# SIXXY_00.net
KiCad netlist of a schematic drawn in Altium Designer
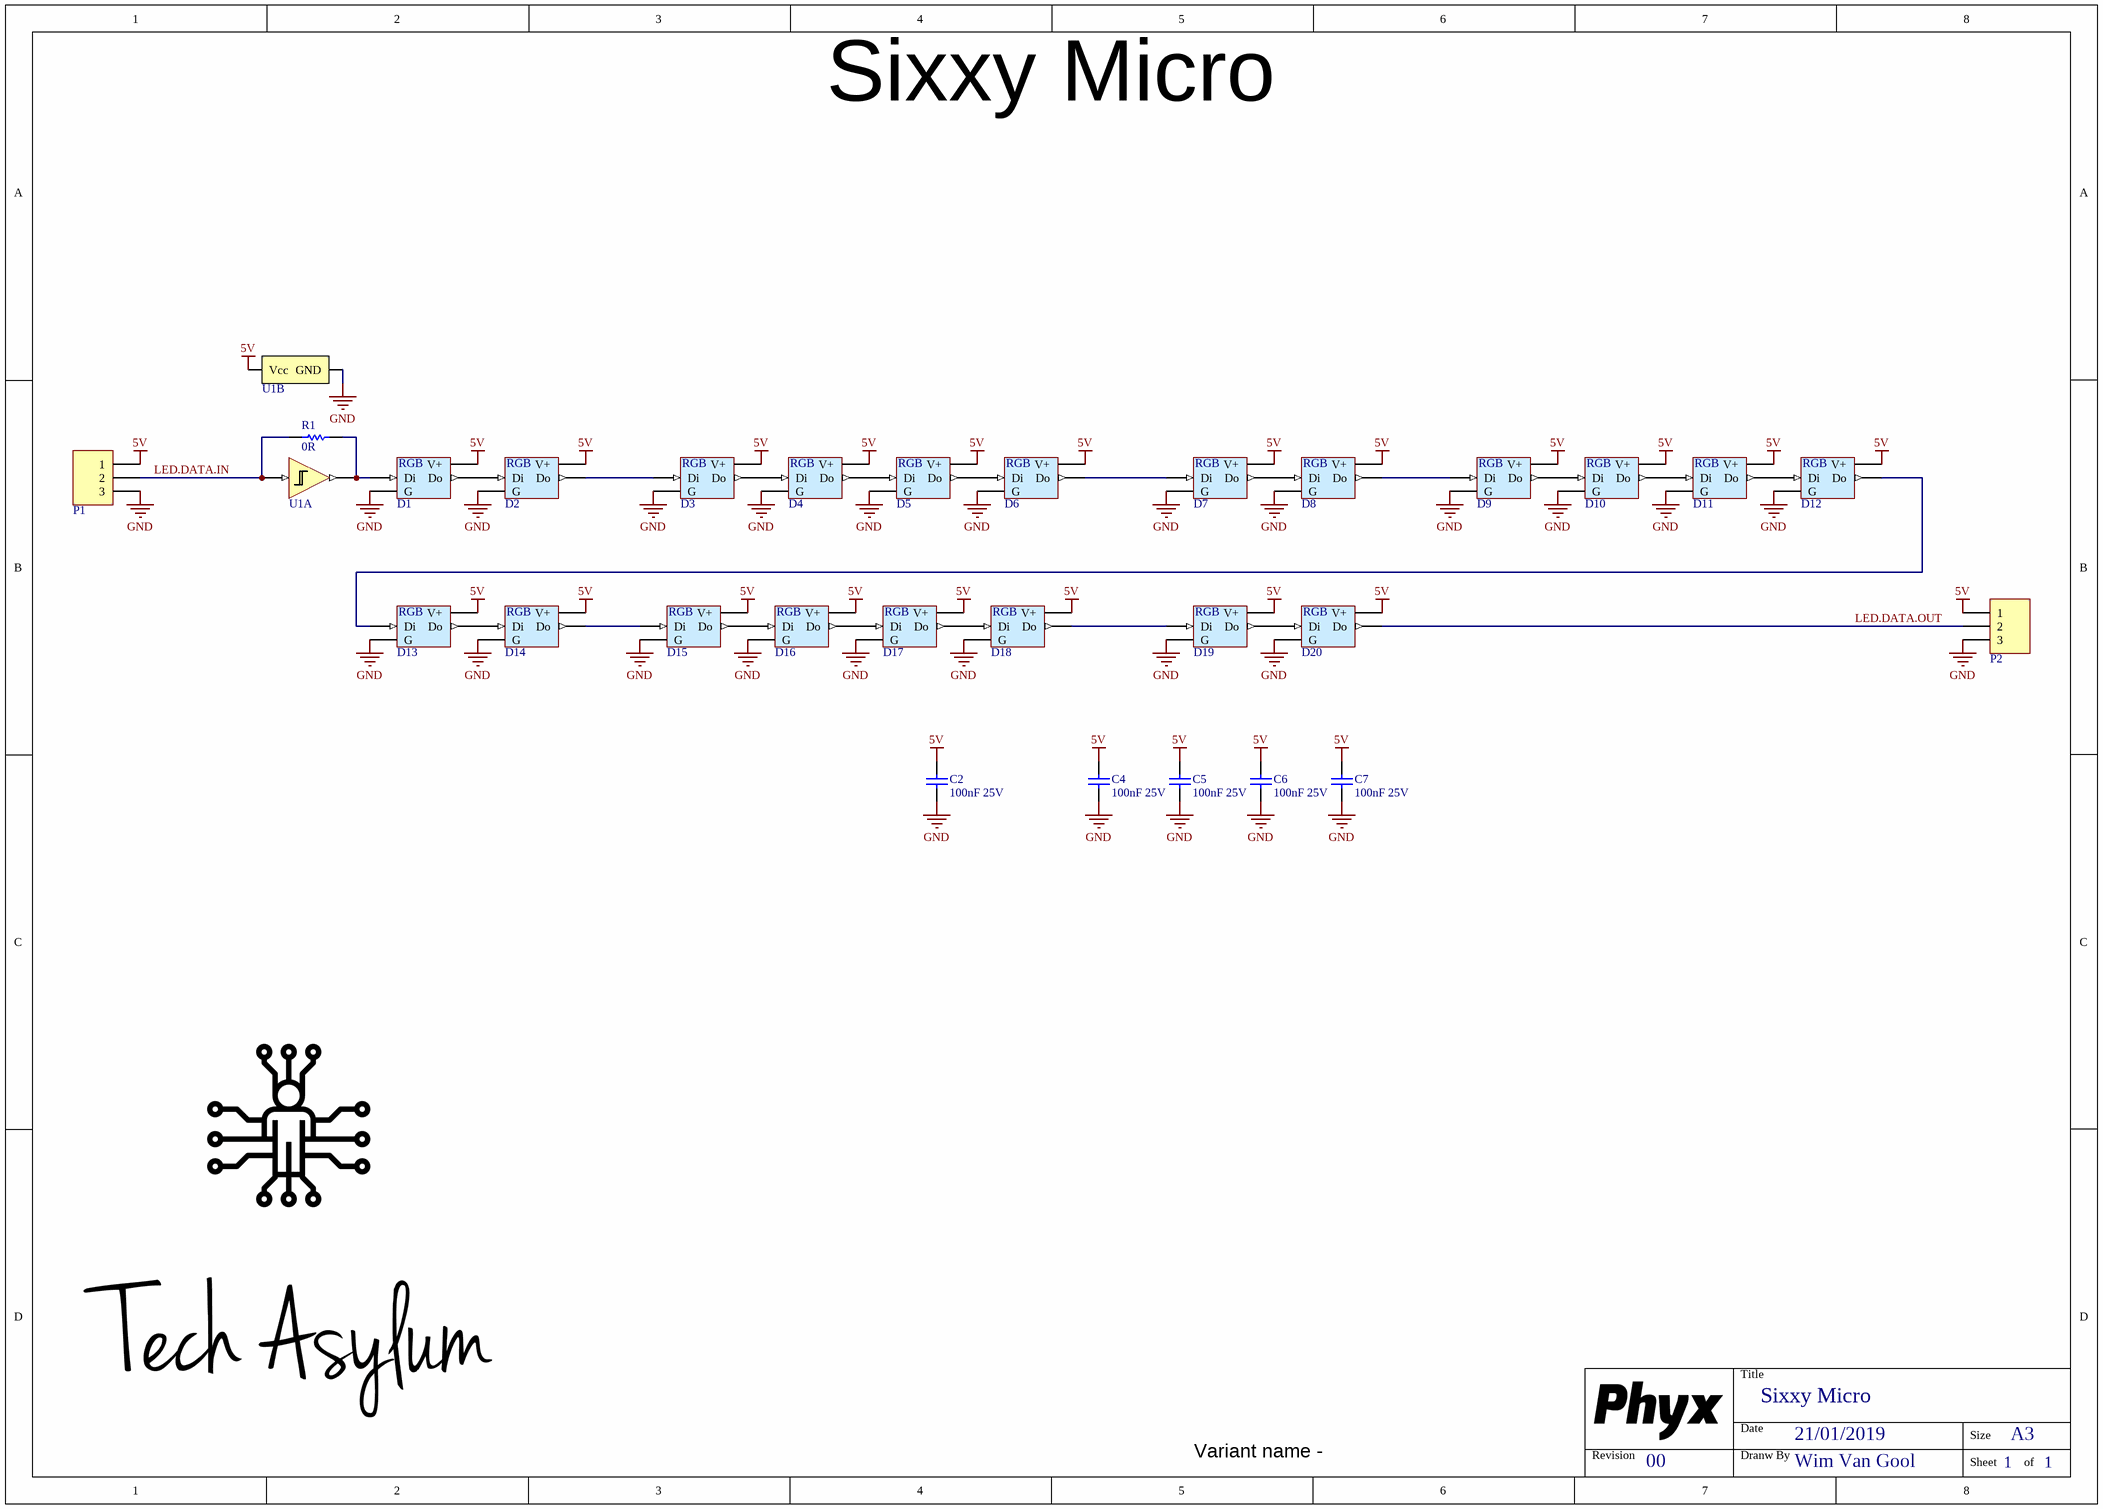
[diagram p0: SIXXY_00.SchDoc]

(export (version "E")
  (design (tool "Eeschema 10.0.6"))
  (components
    (comp (ref "C2")
      (value "100nF 25V")
      (footprint "C0603_N")
      (description "Capacitor Ceramic")
      (fields (field (name "Comment") "CAP_CERAMIC"))
      (libsource (lib "Phyx_Components") (part "CAP_CERAMIC"))
    )
    (comp (ref "C4")
      (value "100nF 25V")
      (footprint "C0603_N")
      (description "Capacitor Ceramic")
      (fields (field (name "Comment") "CAP_CERAMIC"))
      (libsource (lib "Phyx_Components") (part "CAP_CERAMIC"))
    )
    (comp (ref "C5")
      (value "100nF 25V")
      (footprint "C0603_N")
      (description "Capacitor Ceramic")
      (fields (field (name "Comment") "CAP_CERAMIC"))
      (libsource (lib "Phyx_Components") (part "CAP_CERAMIC"))
    )
    (comp (ref "C6")
      (value "100nF 25V")
      (footprint "C0603_N")
      (description "Capacitor Ceramic")
      (fields (field (name "Comment") "CAP_CERAMIC"))
      (libsource (lib "Phyx_Components") (part "CAP_CERAMIC"))
    )
    (comp (ref "C7")
      (value "100nF 25V")
      (footprint "C0603_N")
      (description "Capacitor Ceramic")
      (fields (field (name "Comment") "CAP_CERAMIC"))
      (libsource (lib "Phyx_Components") (part "CAP_CERAMIC"))
    )
    (comp (ref "D1")
      (value "WS2812 based digital RGB LED 2022 package")
      (footprint "LED_2022_WS2812B")
      (description "=Description")
      (libsource (lib "Phyx_Components") (part "LED_RGB_WS2812B_2022"))
    )
    (comp (ref "D2")
      (value "WS2812 based digital RGB LED 2022 package")
      (footprint "LED_2022_WS2812B")
      (description "=Description")
      (libsource (lib "Phyx_Components") (part "LED_RGB_WS2812B_2022"))
    )
    (comp (ref "D3")
      (value "WS2812 based digital RGB LED 2022 package")
      (footprint "LED_2022_WS2812B")
      (description "=Description")
      (libsource (lib "Phyx_Components") (part "LED_RGB_WS2812B_2022"))
    )
    (comp (ref "D4")
      (value "WS2812 based digital RGB LED 2022 package")
      (footprint "LED_2022_WS2812B")
      (description "=Description")
      (libsource (lib "Phyx_Components") (part "LED_RGB_WS2812B_2022"))
    )
    (comp (ref "D5")
      (value "WS2812 based digital RGB LED 2022 package")
      (footprint "LED_2022_WS2812B")
      (description "=Description")
      (libsource (lib "Phyx_Components") (part "LED_RGB_WS2812B_2022"))
    )
    (comp (ref "D6")
      (value "WS2812 based digital RGB LED 2022 package")
      (footprint "LED_2022_WS2812B")
      (description "=Description")
      (libsource (lib "Phyx_Components") (part "LED_RGB_WS2812B_2022"))
    )
    (comp (ref "D7")
      (value "WS2812 based digital RGB LED 2022 package")
      (footprint "LED_2022_WS2812B")
      (description "=Description")
      (libsource (lib "Phyx_Components") (part "LED_RGB_WS2812B_2022"))
    )
    (comp (ref "D8")
      (value "WS2812 based digital RGB LED 2022 package")
      (footprint "LED_2022_WS2812B")
      (description "=Description")
      (libsource (lib "Phyx_Components") (part "LED_RGB_WS2812B_2022"))
    )
    (comp (ref "D9")
      (value "WS2812 based digital RGB LED 2022 package")
      (footprint "LED_2022_WS2812B")
      (description "=Description")
      (libsource (lib "Phyx_Components") (part "LED_RGB_WS2812B_2022"))
    )
    (comp (ref "D10")
      (value "WS2812 based digital RGB LED 2022 package")
      (footprint "LED_2022_WS2812B")
      (description "=Description")
      (libsource (lib "Phyx_Components") (part "LED_RGB_WS2812B_2022"))
    )
    (comp (ref "D11")
      (value "WS2812 based digital RGB LED 2022 package")
      (footprint "LED_2022_WS2812B")
      (description "=Description")
      (libsource (lib "Phyx_Components") (part "LED_RGB_WS2812B_2022"))
    )
    (comp (ref "D12")
      (value "WS2812 based digital RGB LED 2022 package")
      (footprint "LED_2022_WS2812B")
      (description "=Description")
      (libsource (lib "Phyx_Components") (part "LED_RGB_WS2812B_2022"))
    )
    (comp (ref "D13")
      (value "WS2812 based digital RGB LED 2022 package")
      (footprint "LED_2022_WS2812B")
      (description "=Description")
      (libsource (lib "Phyx_Components") (part "LED_RGB_WS2812B_2022"))
    )
    (comp (ref "D14")
      (value "WS2812 based digital RGB LED 2022 package")
      (footprint "LED_2022_WS2812B")
      (description "=Description")
      (libsource (lib "Phyx_Components") (part "LED_RGB_WS2812B_2022"))
    )
    (comp (ref "D15")
      (value "WS2812 based digital RGB LED 2022 package")
      (footprint "LED_2022_WS2812B")
      (description "=Description")
      (libsource (lib "Phyx_Components") (part "LED_RGB_WS2812B_2022"))
    )
    (comp (ref "D16")
      (value "WS2812 based digital RGB LED 2022 package")
      (footprint "LED_2022_WS2812B")
      (description "=Description")
      (libsource (lib "Phyx_Components") (part "LED_RGB_WS2812B_2022"))
    )
    (comp (ref "D17")
      (value "WS2812 based digital RGB LED 2022 package")
      (footprint "LED_2022_WS2812B")
      (description "=Description")
      (libsource (lib "Phyx_Components") (part "LED_RGB_WS2812B_2022"))
    )
    (comp (ref "D18")
      (value "WS2812 based digital RGB LED 2022 package")
      (footprint "LED_2022_WS2812B")
      (description "=Description")
      (libsource (lib "Phyx_Components") (part "LED_RGB_WS2812B_2022"))
    )
    (comp (ref "D19")
      (value "WS2812 based digital RGB LED 2022 package")
      (footprint "LED_2022_WS2812B")
      (description "=Description")
      (libsource (lib "Phyx_Components") (part "LED_RGB_WS2812B_2022"))
    )
    (comp (ref "D20")
      (value "WS2812 based digital RGB LED 2022 package")
      (footprint "LED_2022_WS2812B")
      (description "=Description")
      (libsource (lib "Phyx_Components") (part "LED_RGB_WS2812B_2022"))
    )
    (comp (ref "P1")
      (value "Header 1.0mm RA Shrouded 3")
      (footprint "WE_665103131822")
      (libsource (lib "Phyx_Components") (part "Header 3"))
    )
    (comp (ref "P2")
      (value "Header 1.0mm RA Shrouded 3")
      (footprint "WE_665103131822")
      (libsource (lib "") (part "Header 3_1"))
    )
    (comp (ref "R1")
      (value "0R")
      (footprint "R0603_N")
      (fields (field (name "Comment") "RESISTOR"))
      (libsource (lib "Phyx_Components") (part "RESISTOR"))
    )
    (comp (ref "U1")
      (value "SN74LVC1G17DCKR  Buffer, Schmitt Trigger, 1.65V to 5.5V")
      (footprint "TI_DCK_R-PDSO-G5")
      (description "=Description")
      (libsource (lib "Phyx_Components") (part "SN74LVC1G17DCKR"))
    )
  )
  (nets
    (net (code "1") (name "/LED.DATA.IN") (class "Default")
      (node (ref "P1") (pin "2") (pinfunction "2_2") (pintype "passive"))
      (node (ref "R1") (pin "2") (pinfunction "2_2") (pintype "passive"))
      (node (ref "U1") (pin "2") (pinfunction "A_2") (pintype "input"))
    )
    (net (code "2") (name "/LED.DATA.OUT") (class "Default")
      (node (ref "D20") (pin "1") (pinfunction "Do_1") (pintype "output"))
      (node (ref "P2") (pin "2") (pinfunction "2_2") (pintype "passive"))
    )
    (net (code "3") (name "5V") (class "Default")
      (node (ref "C2") (pin "1") (pinfunction "1_1") (pintype "passive"))
      (node (ref "C4") (pin "1") (pinfunction "1_1") (pintype "passive"))
      (node (ref "C5") (pin "1") (pinfunction "1_1") (pintype "passive"))
      (node (ref "C6") (pin "1") (pinfunction "1_1") (pintype "passive"))
      (node (ref "C7") (pin "1") (pinfunction "1_1") (pintype "passive"))
      (node (ref "D1") (pin "4") (pinfunction "V+_4") (pintype "power_in"))
      (node (ref "D10") (pin "4") (pinfunction "V+_4") (pintype "power_in"))
      (node (ref "D11") (pin "4") (pinfunction "V+_4") (pintype "power_in"))
      (node (ref "D12") (pin "4") (pinfunction "V+_4") (pintype "power_in"))
      (node (ref "D13") (pin "4") (pinfunction "V+_4") (pintype "power_in"))
      (node (ref "D14") (pin "4") (pinfunction "V+_4") (pintype "power_in"))
      (node (ref "D15") (pin "4") (pinfunction "V+_4") (pintype "power_in"))
      (node (ref "D16") (pin "4") (pinfunction "V+_4") (pintype "power_in"))
      (node (ref "D17") (pin "4") (pinfunction "V+_4") (pintype "power_in"))
      (node (ref "D18") (pin "4") (pinfunction "V+_4") (pintype "power_in"))
      (node (ref "D19") (pin "4") (pinfunction "V+_4") (pintype "power_in"))
      (node (ref "D2") (pin "4") (pinfunction "V+_4") (pintype "power_in"))
      (node (ref "D20") (pin "4") (pinfunction "V+_4") (pintype "power_in"))
      (node (ref "D3") (pin "4") (pinfunction "V+_4") (pintype "power_in"))
      (node (ref "D4") (pin "4") (pinfunction "V+_4") (pintype "power_in"))
      (node (ref "D5") (pin "4") (pinfunction "V+_4") (pintype "power_in"))
      (node (ref "D6") (pin "4") (pinfunction "V+_4") (pintype "power_in"))
      (node (ref "D7") (pin "4") (pinfunction "V+_4") (pintype "power_in"))
      (node (ref "D8") (pin "4") (pinfunction "V+_4") (pintype "power_in"))
      (node (ref "D9") (pin "4") (pinfunction "V+_4") (pintype "power_in"))
      (node (ref "P1") (pin "1") (pinfunction "1_1") (pintype "passive"))
      (node (ref "P2") (pin "1") (pinfunction "1_1") (pintype "passive"))
      (node (ref "U1") (pin "5") (pinfunction "Vcc_5") (pintype "power_in"))
    )
    (net (code "4") (name "GND") (class "Default")
      (node (ref "C2") (pin "2") (pinfunction "2_2") (pintype "passive"))
      (node (ref "C4") (pin "2") (pinfunction "2_2") (pintype "passive"))
      (node (ref "C5") (pin "2") (pinfunction "2_2") (pintype "passive"))
      (node (ref "C6") (pin "2") (pinfunction "2_2") (pintype "passive"))
      (node (ref "C7") (pin "2") (pinfunction "2_2") (pintype "passive"))
      (node (ref "D1") (pin "2") (pinfunction "G_2") (pintype "power_in"))
      (node (ref "D10") (pin "2") (pinfunction "G_2") (pintype "power_in"))
      (node (ref "D11") (pin "2") (pinfunction "G_2") (pintype "power_in"))
      (node (ref "D12") (pin "2") (pinfunction "G_2") (pintype "power_in"))
      (node (ref "D13") (pin "2") (pinfunction "G_2") (pintype "power_in"))
      (node (ref "D14") (pin "2") (pinfunction "G_2") (pintype "power_in"))
      (node (ref "D15") (pin "2") (pinfunction "G_2") (pintype "power_in"))
      (node (ref "D16") (pin "2") (pinfunction "G_2") (pintype "power_in"))
      (node (ref "D17") (pin "2") (pinfunction "G_2") (pintype "power_in"))
      (node (ref "D18") (pin "2") (pinfunction "G_2") (pintype "power_in"))
      (node (ref "D19") (pin "2") (pinfunction "G_2") (pintype "power_in"))
      (node (ref "D2") (pin "2") (pinfunction "G_2") (pintype "power_in"))
      (node (ref "D20") (pin "2") (pinfunction "G_2") (pintype "power_in"))
      (node (ref "D3") (pin "2") (pinfunction "G_2") (pintype "power_in"))
      (node (ref "D4") (pin "2") (pinfunction "G_2") (pintype "power_in"))
      (node (ref "D5") (pin "2") (pinfunction "G_2") (pintype "power_in"))
      (node (ref "D6") (pin "2") (pinfunction "G_2") (pintype "power_in"))
      (node (ref "D7") (pin "2") (pinfunction "G_2") (pintype "power_in"))
      (node (ref "D8") (pin "2") (pinfunction "G_2") (pintype "power_in"))
      (node (ref "D9") (pin "2") (pinfunction "G_2") (pintype "power_in"))
      (node (ref "P1") (pin "3") (pinfunction "3_3") (pintype "passive"))
      (node (ref "P2") (pin "3") (pinfunction "3_3") (pintype "passive"))
      (node (ref "U1") (pin "3") (pinfunction "GND_3") (pintype "power_in"))
    )
    (net (code "5") (name "Net-(D1-Di)") (class "Default")
      (node (ref "D1") (pin "3") (pinfunction "Di_3") (pintype "input"))
      (node (ref "R1") (pin "1") (pinfunction "1_1") (pintype "passive"))
      (node (ref "U1") (pin "4") (pinfunction "Y_4") (pintype "output"))
    )
    (net (code "6") (name "Net-(D1-Do)") (class "Default")
      (node (ref "D1") (pin "1") (pinfunction "Do_1") (pintype "output"))
      (node (ref "D2") (pin "3") (pinfunction "Di_3") (pintype "input"))
    )
    (net (code "7") (name "Net-(D2-Do)") (class "Default")
      (node (ref "D2") (pin "1") (pinfunction "Do_1") (pintype "output"))
      (node (ref "D3") (pin "3") (pinfunction "Di_3") (pintype "input"))
    )
    (net (code "8") (name "Net-(D3-Do)") (class "Default")
      (node (ref "D3") (pin "1") (pinfunction "Do_1") (pintype "output"))
      (node (ref "D4") (pin "3") (pinfunction "Di_3") (pintype "input"))
    )
    (net (code "9") (name "Net-(D4-Do)") (class "Default")
      (node (ref "D4") (pin "1") (pinfunction "Do_1") (pintype "output"))
      (node (ref "D5") (pin "3") (pinfunction "Di_3") (pintype "input"))
    )
    (net (code "10") (name "Net-(D5-Do)") (class "Default")
      (node (ref "D5") (pin "1") (pinfunction "Do_1") (pintype "output"))
      (node (ref "D6") (pin "3") (pinfunction "Di_3") (pintype "input"))
    )
    (net (code "11") (name "Net-(D6-Do)") (class "Default")
      (node (ref "D6") (pin "1") (pinfunction "Do_1") (pintype "output"))
      (node (ref "D7") (pin "3") (pinfunction "Di_3") (pintype "input"))
    )
    (net (code "12") (name "Net-(D7-Do)") (class "Default")
      (node (ref "D7") (pin "1") (pinfunction "Do_1") (pintype "output"))
      (node (ref "D8") (pin "3") (pinfunction "Di_3") (pintype "input"))
    )
    (net (code "13") (name "Net-(D8-Do)") (class "Default")
      (node (ref "D8") (pin "1") (pinfunction "Do_1") (pintype "output"))
      (node (ref "D9") (pin "3") (pinfunction "Di_3") (pintype "input"))
    )
    (net (code "14") (name "Net-(D10-Di)") (class "Default")
      (node (ref "D10") (pin "3") (pinfunction "Di_3") (pintype "input"))
      (node (ref "D9") (pin "1") (pinfunction "Do_1") (pintype "output"))
    )
    (net (code "15") (name "Net-(D10-Do)") (class "Default")
      (node (ref "D10") (pin "1") (pinfunction "Do_1") (pintype "output"))
      (node (ref "D11") (pin "3") (pinfunction "Di_3") (pintype "input"))
    )
    (net (code "16") (name "Net-(D11-Do)") (class "Default")
      (node (ref "D11") (pin "1") (pinfunction "Do_1") (pintype "output"))
      (node (ref "D12") (pin "3") (pinfunction "Di_3") (pintype "input"))
    )
    (net (code "17") (name "Net-(D12-Do)") (class "Default")
      (node (ref "D12") (pin "1") (pinfunction "Do_1") (pintype "output"))
      (node (ref "D13") (pin "3") (pinfunction "Di_3") (pintype "input"))
    )
    (net (code "18") (name "Net-(D13-Do)") (class "Default")
      (node (ref "D13") (pin "1") (pinfunction "Do_1") (pintype "output"))
      (node (ref "D14") (pin "3") (pinfunction "Di_3") (pintype "input"))
    )
    (net (code "19") (name "Net-(D14-Do)") (class "Default")
      (node (ref "D14") (pin "1") (pinfunction "Do_1") (pintype "output"))
      (node (ref "D15") (pin "3") (pinfunction "Di_3") (pintype "input"))
    )
    (net (code "20") (name "Net-(D15-Do)") (class "Default")
      (node (ref "D15") (pin "1") (pinfunction "Do_1") (pintype "output"))
      (node (ref "D16") (pin "3") (pinfunction "Di_3") (pintype "input"))
    )
    (net (code "21") (name "Net-(D16-Do)") (class "Default")
      (node (ref "D16") (pin "1") (pinfunction "Do_1") (pintype "output"))
      (node (ref "D17") (pin "3") (pinfunction "Di_3") (pintype "input"))
    )
    (net (code "22") (name "Net-(D17-Do)") (class "Default")
      (node (ref "D17") (pin "1") (pinfunction "Do_1") (pintype "output"))
      (node (ref "D18") (pin "3") (pinfunction "Di_3") (pintype "input"))
    )
    (net (code "23") (name "Net-(D18-Do)") (class "Default")
      (node (ref "D18") (pin "1") (pinfunction "Do_1") (pintype "output"))
      (node (ref "D19") (pin "3") (pinfunction "Di_3") (pintype "input"))
    )
    (net (code "24") (name "Net-(D19-Do)") (class "Default")
      (node (ref "D19") (pin "1") (pinfunction "Do_1") (pintype "output"))
      (node (ref "D20") (pin "3") (pinfunction "Di_3") (pintype "input"))
    )
  )
)
